# interface.net
KiCad netlist of a schematic drawn in Altium Designer
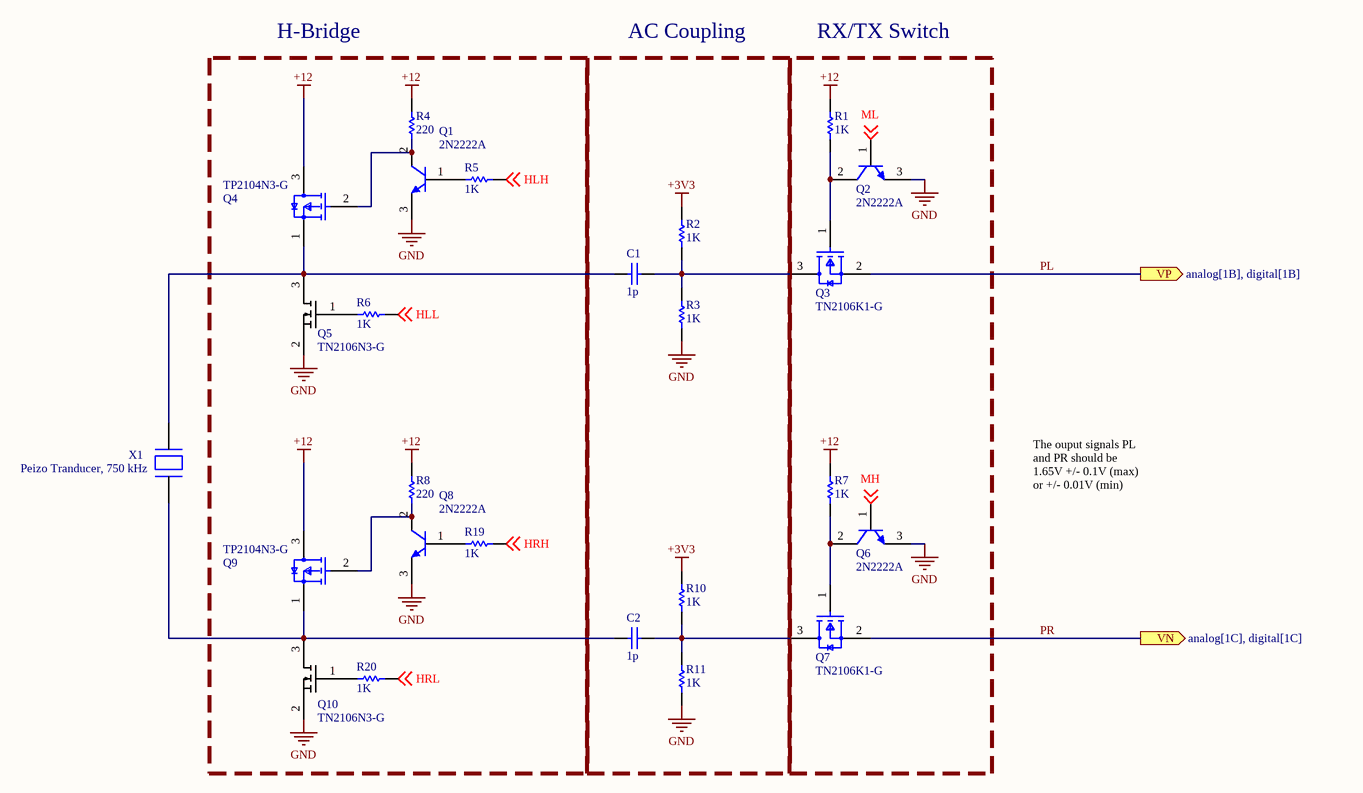
[diagram p0: interface.SchDoc]

(export (version "E")
  (design (tool "Eeschema 10.0.6"))
  (components
    (comp (ref "C1")
      (value "1p")
      (description "Capacitor")
      (libsource (lib "Simulation Generic Components") (part "Capacitor"))
    )
    (comp (ref "C2")
      (value "1p")
      (description "Capacitor")
      (libsource (lib "Simulation Generic Components") (part "Capacitor"))
    )
    (comp (ref "Q1")
      (value "2N2222A")
      (footprint "STM-TO-18-3")
      (description "High Speed Switch, 0.6 A IC, -65 to 175 degC, 3-Pin TO-18, RoHS, Bulk")
      (fields (field (name "MANUFACTURER") "STMicroelectronics"))
      (libsource (lib "Altium Content Vault") (part "NPN_B1C2E3-3"))
    )
    (comp (ref "Q2")
      (value "2N2222A")
      (footprint "STM-TO-18-3")
      (description "High Speed Switch, 0.6 A IC, -65 to 175 degC, 3-Pin TO-18, RoHS, Bulk")
      (fields (field (name "MANUFACTURER") "STMicroelectronics"))
      (libsource (lib "Altium Content Vault") (part "NPN_B1C2E3-3"))
    )
    (comp (ref "Q3")
      (value "TN2106K1-G")
      (footprint "FP-K1-T-IPC_A")
      (description "MOSFET N-CH 60V 280MA SOT23-3")
      (libsource (lib "Altium Content Vault") (part "91ce4ddf2aa298de9e82d3904de0f67"))
    )
    (comp (ref "Q4")
      (value "TP2104N3-G")
      (footprint "FP-TP2104N3-G-MFG")
      (description "MOSFET P-CH 40V 175MA TO92-3")
      (libsource (lib "Altium Content Vault") (part "9a74f65b4248df6e06e844fd3676475"))
    )
    (comp (ref "Q5")
      (value "TN2106N3-G")
      (fields (field (name "MANUFACTURER") "Microchip Supertex"))
      (libsource (lib "dvl") (part "TN2106N3-G"))
    )
    (comp (ref "Q6")
      (value "2N2222A")
      (footprint "STM-TO-18-3")
      (description "High Speed Switch, 0.6 A IC, -65 to 175 degC, 3-Pin TO-18, RoHS, Bulk")
      (fields (field (name "MANUFACTURER") "STMicroelectronics"))
      (libsource (lib "Altium Content Vault") (part "NPN_B1C2E3-3"))
    )
    (comp (ref "Q7")
      (value "TN2106K1-G")
      (footprint "FP-K1-T-IPC_A")
      (description "MOSFET N-CH 60V 280MA SOT23-3")
      (libsource (lib "Altium Content Vault") (part "91ce4ddf2aa298de9e82d3904de0f67"))
    )
    (comp (ref "Q8")
      (value "2N2222A")
      (footprint "STM-TO-18-3")
      (description "High Speed Switch, 0.6 A IC, -65 to 175 degC, 3-Pin TO-18, RoHS, Bulk")
      (fields (field (name "MANUFACTURER") "STMicroelectronics"))
      (libsource (lib "Altium Content Vault") (part "NPN_B1C2E3-3"))
    )
    (comp (ref "Q9")
      (value "TP2104N3-G")
      (footprint "FP-TP2104N3-G-MFG")
      (description "MOSFET P-CH 40V 175MA TO92-3")
      (libsource (lib "Altium Content Vault") (part "9a74f65b4248df6e06e844fd3676475"))
    )
    (comp (ref "Q10")
      (value "TN2106N3-G")
      (fields (field (name "MANUFACTURER") "Microchip Supertex"))
      (libsource (lib "dvl") (part "TN2106N3-G"))
    )
    (comp (ref "R1")
      (value "1K")
      (description "Resistor")
      (libsource (lib "Simulation Generic Components") (part "Resistor"))
    )
    (comp (ref "R2")
      (value "1K")
      (description "Resistor")
      (libsource (lib "Simulation Generic Components") (part "Resistor"))
    )
    (comp (ref "R3")
      (value "1K")
      (description "Resistor")
      (libsource (lib "Simulation Generic Components") (part "Resistor"))
    )
    (comp (ref "R4")
      (value "220")
      (description "Resistor")
      (libsource (lib "Simulation Generic Components") (part "Resistor"))
    )
    (comp (ref "R5")
      (value "1K")
      (description "Resistor")
      (libsource (lib "Simulation Generic Components") (part "Resistor"))
    )
    (comp (ref "R6")
      (value "1K")
      (description "Resistor")
      (libsource (lib "Simulation Generic Components") (part "Resistor"))
    )
    (comp (ref "R7")
      (value "1K")
      (description "Resistor")
      (libsource (lib "Simulation Generic Components") (part "Resistor"))
    )
    (comp (ref "R8")
      (value "220")
      (description "Resistor")
      (libsource (lib "Simulation Generic Components") (part "Resistor"))
    )
    (comp (ref "R10")
      (value "1K")
      (description "Resistor")
      (libsource (lib "Simulation Generic Components") (part "Resistor"))
    )
    (comp (ref "R11")
      (value "1K")
      (description "Resistor")
      (libsource (lib "Simulation Generic Components") (part "Resistor"))
    )
    (comp (ref "R19")
      (value "1K")
      (description "Resistor")
      (libsource (lib "Simulation Generic Components") (part "Resistor"))
    )
    (comp (ref "R20")
      (value "1K")
      (description "Resistor")
      (libsource (lib "Simulation Generic Components") (part "Resistor"))
    )
    (comp (ref "X1") (value "Peizo Tranducer, 750 kHz") (libsource (lib "dvl") (part "SMD20T27F750S")))
  )
  (nets
    (net (code "1") (name "+3V3") (class "Default")
      (node (ref "R10") (pin "2") (pinfunction "2_2") (pintype "passive"))
      (node (ref "R2") (pin "2") (pinfunction "2_2") (pintype "passive"))
    )
    (net (code "2") (name "+12") (class "Default")
      (node (ref "Q4") (pin "3") (pinfunction "Drain_3") (pintype "passive"))
      (node (ref "Q9") (pin "3") (pinfunction "Drain_3") (pintype "passive"))
      (node (ref "R1") (pin "2") (pinfunction "2_2") (pintype "passive"))
      (node (ref "R4") (pin "2") (pinfunction "2_2") (pintype "passive"))
      (node (ref "R7") (pin "2") (pinfunction "2_2") (pintype "passive"))
      (node (ref "R8") (pin "2") (pinfunction "2_2") (pintype "passive"))
    )
    (net (code "3") (name "/PL") (class "Default")
      (node (ref "Q3") (pin "2") (pinfunction "Source_2") (pintype "passive"))
    )
    (net (code "4") (name "/PR") (class "Default")
      (node (ref "Q7") (pin "2") (pinfunction "Source_2") (pintype "passive"))
    )
    (net (code "5") (name "GND") (class "Default")
      (node (ref "Q1") (pin "3") (pinfunction "E_3") (pintype "passive"))
      (node (ref "Q10") (pin "2") (pinfunction "S_2") (pintype "passive"))
      (node (ref "Q2") (pin "3") (pinfunction "E_3") (pintype "passive"))
      (node (ref "Q5") (pin "2") (pinfunction "S_2") (pintype "passive"))
      (node (ref "Q6") (pin "3") (pinfunction "E_3") (pintype "passive"))
      (node (ref "Q8") (pin "3") (pinfunction "E_3") (pintype "passive"))
      (node (ref "R11") (pin "1") (pinfunction "1_1") (pintype "passive"))
      (node (ref "R3") (pin "1") (pinfunction "1_1") (pintype "passive"))
    )
    (net (code "6") (name "HLH") (class "Default")
      (node (ref "R5") (pin "1") (pinfunction "1_1") (pintype "passive"))
    )
    (net (code "7") (name "HLL") (class "Default")
      (node (ref "R6") (pin "1") (pinfunction "1_1") (pintype "passive"))
    )
    (net (code "8") (name "HRH") (class "Default")
      (node (ref "R19") (pin "1") (pinfunction "1_1") (pintype "passive"))
    )
    (net (code "9") (name "HRL") (class "Default")
      (node (ref "R20") (pin "1") (pinfunction "1_1") (pintype "passive"))
    )
    (net (code "10") (name "MH") (class "Default")
      (node (ref "Q6") (pin "1") (pinfunction "B_1") (pintype "passive"))
    )
    (net (code "11") (name "ML") (class "Default")
      (node (ref "Q2") (pin "1") (pinfunction "B_1") (pintype "passive"))
    )
    (net (code "12") (name "Net-(Q1-B)") (class "Default")
      (node (ref "Q1") (pin "1") (pinfunction "B_1") (pintype "passive"))
      (node (ref "R5") (pin "2") (pinfunction "2_2") (pintype "passive"))
    )
    (net (code "13") (name "Net-(Q1-C)") (class "Default")
      (node (ref "Q1") (pin "2") (pinfunction "C_2") (pintype "passive"))
      (node (ref "Q4") (pin "2") (pinfunction "Gate_2") (pintype "passive"))
      (node (ref "R4") (pin "1") (pinfunction "1_1") (pintype "passive"))
    )
    (net (code "14") (name "Net-(Q2-C)") (class "Default")
      (node (ref "Q2") (pin "2") (pinfunction "C_2") (pintype "passive"))
      (node (ref "Q3") (pin "1") (pinfunction "Gate_1") (pintype "passive"))
      (node (ref "R1") (pin "1") (pinfunction "1_1") (pintype "passive"))
    )
    (net (code "15") (name "Net-(Q3-Drain)") (class "Default")
      (node (ref "C1") (pin "2") (pinfunction "2_2") (pintype "passive"))
      (node (ref "Q3") (pin "3") (pinfunction "Drain_3") (pintype "passive"))
      (node (ref "R2") (pin "1") (pinfunction "1_1") (pintype "passive"))
      (node (ref "R3") (pin "2") (pinfunction "2_2") (pintype "passive"))
    )
    (net (code "16") (name "Net-(Q4-Source)") (class "Default")
      (node (ref "C1") (pin "1") (pinfunction "1_1") (pintype "passive"))
      (node (ref "Q4") (pin "1") (pinfunction "Source_1") (pintype "passive"))
      (node (ref "Q5") (pin "3") (pinfunction "D_3") (pintype "passive"))
      (node (ref "X1") (pin "1") (pinfunction "1_1") (pintype "passive"))
    )
    (net (code "17") (name "Net-(Q5-G)") (class "Default")
      (node (ref "Q5") (pin "1") (pinfunction "G_1") (pintype "passive"))
      (node (ref "R6") (pin "2") (pinfunction "2_2") (pintype "passive"))
    )
    (net (code "18") (name "Net-(Q6-C)") (class "Default")
      (node (ref "Q6") (pin "2") (pinfunction "C_2") (pintype "passive"))
      (node (ref "Q7") (pin "1") (pinfunction "Gate_1") (pintype "passive"))
      (node (ref "R7") (pin "1") (pinfunction "1_1") (pintype "passive"))
    )
    (net (code "19") (name "Net-(Q7-Drain)") (class "Default")
      (node (ref "C2") (pin "2") (pinfunction "2_2") (pintype "passive"))
      (node (ref "Q7") (pin "3") (pinfunction "Drain_3") (pintype "passive"))
      (node (ref "R10") (pin "1") (pinfunction "1_1") (pintype "passive"))
      (node (ref "R11") (pin "2") (pinfunction "2_2") (pintype "passive"))
    )
    (net (code "20") (name "Net-(Q8-B)") (class "Default")
      (node (ref "Q8") (pin "1") (pinfunction "B_1") (pintype "passive"))
      (node (ref "R19") (pin "2") (pinfunction "2_2") (pintype "passive"))
    )
    (net (code "21") (name "Net-(Q8-C)") (class "Default")
      (node (ref "Q8") (pin "2") (pinfunction "C_2") (pintype "passive"))
      (node (ref "Q9") (pin "2") (pinfunction "Gate_2") (pintype "passive"))
      (node (ref "R8") (pin "1") (pinfunction "1_1") (pintype "passive"))
    )
    (net (code "22") (name "Net-(Q10-D)") (class "Default")
      (node (ref "C2") (pin "1") (pinfunction "1_1") (pintype "passive"))
      (node (ref "Q10") (pin "3") (pinfunction "D_3") (pintype "passive"))
      (node (ref "Q9") (pin "1") (pinfunction "Source_1") (pintype "passive"))
      (node (ref "X1") (pin "2") (pinfunction "2_2") (pintype "passive"))
    )
    (net (code "23") (name "Net-(Q10-G)") (class "Default")
      (node (ref "Q10") (pin "1") (pinfunction "G_1") (pintype "passive"))
      (node (ref "R20") (pin "2") (pinfunction "2_2") (pintype "passive"))
    )
  )
)
